# IMU.net
KiCad netlist of a schematic drawn in Altium Designer
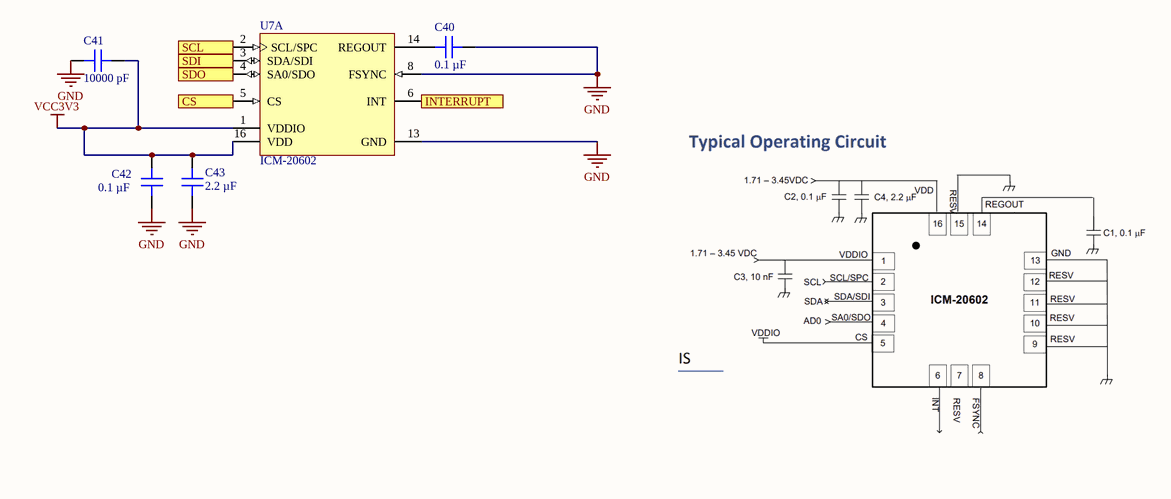
[diagram p0: IMU.SchDoc]

(export (version "E")
  (design (tool "Eeschema 10.0.6"))
  (components
    (comp (ref "C40")
      (value "0.1 µF")
      (footprint "CAP 0603_1608")
      (description "CAP CER 0.1UF 50V X7R 0603")
      (fields (field (name "PART NUMBER") "C0603C104K5RAC7411") (field (name "MANUFACTURER") "KEMET"))
      (libsource (lib "Celestial Altium Library - altium_library") (part "Capacitor"))
    )
    (comp (ref "C41")
      (value "10000 pF")
      (footprint "CAP 0603_1608")
      (description "CAP CER 0603 10NF 16V X7R 10%")
      (fields (field (name "PART NUMBER") "C0603C103K4RECAUTO") (field (name "MANUFACTURER") "KEMET"))
      (libsource (lib "Celestial Altium Library - altium_library") (part "Capacitor"))
    )
    (comp (ref "C42")
      (value "0.1 µF")
      (footprint "CAP 0603_1608")
      (description "CAP CER 0.1UF 50V X7R 0603")
      (fields (field (name "PART NUMBER") "C0603C104K5RAC7411") (field (name "MANUFACTURER") "KEMET"))
      (libsource (lib "Celestial Altium Library - altium_library") (part "Capacitor"))
    )
    (comp (ref "C43")
      (value "2.2 µF")
      (footprint "CAP 0603_1608")
      (description "CAP CER 2.2UF 10V Y5V 0603")
      (fields (field (name "PART NUMBER") "CC0603ZRY5V6BB225") (field (name "MANUFACTURER") "Yageo"))
      (libsource (lib "Celestial Altium Library - altium_library") (part "Capacitor"))
    )
    (comp (ref "U7")
      (value "ICM-20602")
      (footprint "INSE-I62-16")
      (fields (field (name "MANUFACTURER") "InvenSense"))
      (libsource (lib "Altium Content Vault") (part "INSE-ICM-20602-16"))
    )
  )
  (nets
    (net (code "1") (name "/CS") (class "Default")
      (node (ref "U7") (pin "5") (pinfunction "CS_5") (pintype "input"))
    )
    (net (code "2") (name "/INTERRUPT") (class "Default")
      (node (ref "U7") (pin "6") (pinfunction "INT_6") (pintype "open_collector"))
    )
    (net (code "3") (name "/SCL") (class "Default")
      (node (ref "U7") (pin "2") (pinfunction "SCL/SPC_2") (pintype "input"))
    )
    (net (code "4") (name "/SDI") (class "Default")
      (node (ref "U7") (pin "3") (pinfunction "SDA/SDI_3") (pintype "bidirectional"))
    )
    (net (code "5") (name "/SDO") (class "Default")
      (node (ref "U7") (pin "4") (pinfunction "SA0/SDO_4") (pintype "bidirectional"))
    )
    (net (code "6") (name "GND") (class "Default")
      (node (ref "C40") (pin "2") (pinfunction "2_2") (pintype "passive"))
      (node (ref "C41") (pin "1") (pinfunction "1_1") (pintype "passive"))
      (node (ref "C42") (pin "1") (pinfunction "1_1") (pintype "passive"))
      (node (ref "C43") (pin "1") (pinfunction "1_1") (pintype "passive"))
      (node (ref "U7") (pin "13") (pinfunction "GND_13") (pintype "power_in"))
      (node (ref "U7") (pin "8") (pinfunction "FSYNC_8") (pintype "input"))
    )
    (net (code "7") (name "Net-(U7A-REGOUT)") (class "Default")
      (node (ref "C40") (pin "1") (pinfunction "1_1") (pintype "passive"))
      (node (ref "U7") (pin "14") (pinfunction "REGOUT_14") (pintype "passive"))
    )
    (net (code "8") (name "VCC3V3") (class "Default")
      (node (ref "C41") (pin "2") (pinfunction "2_2") (pintype "passive"))
      (node (ref "C42") (pin "2") (pinfunction "2_2") (pintype "passive"))
      (node (ref "C43") (pin "2") (pinfunction "2_2") (pintype "passive"))
      (node (ref "U7") (pin "1") (pinfunction "VDDIO_1") (pintype "power_in"))
      (node (ref "U7") (pin "16") (pinfunction "VDD_16") (pintype "power_in"))
    )
  )
)
